# SimpleEXGCircuit.net
KiCad netlist of a schematic drawn in EAGLE
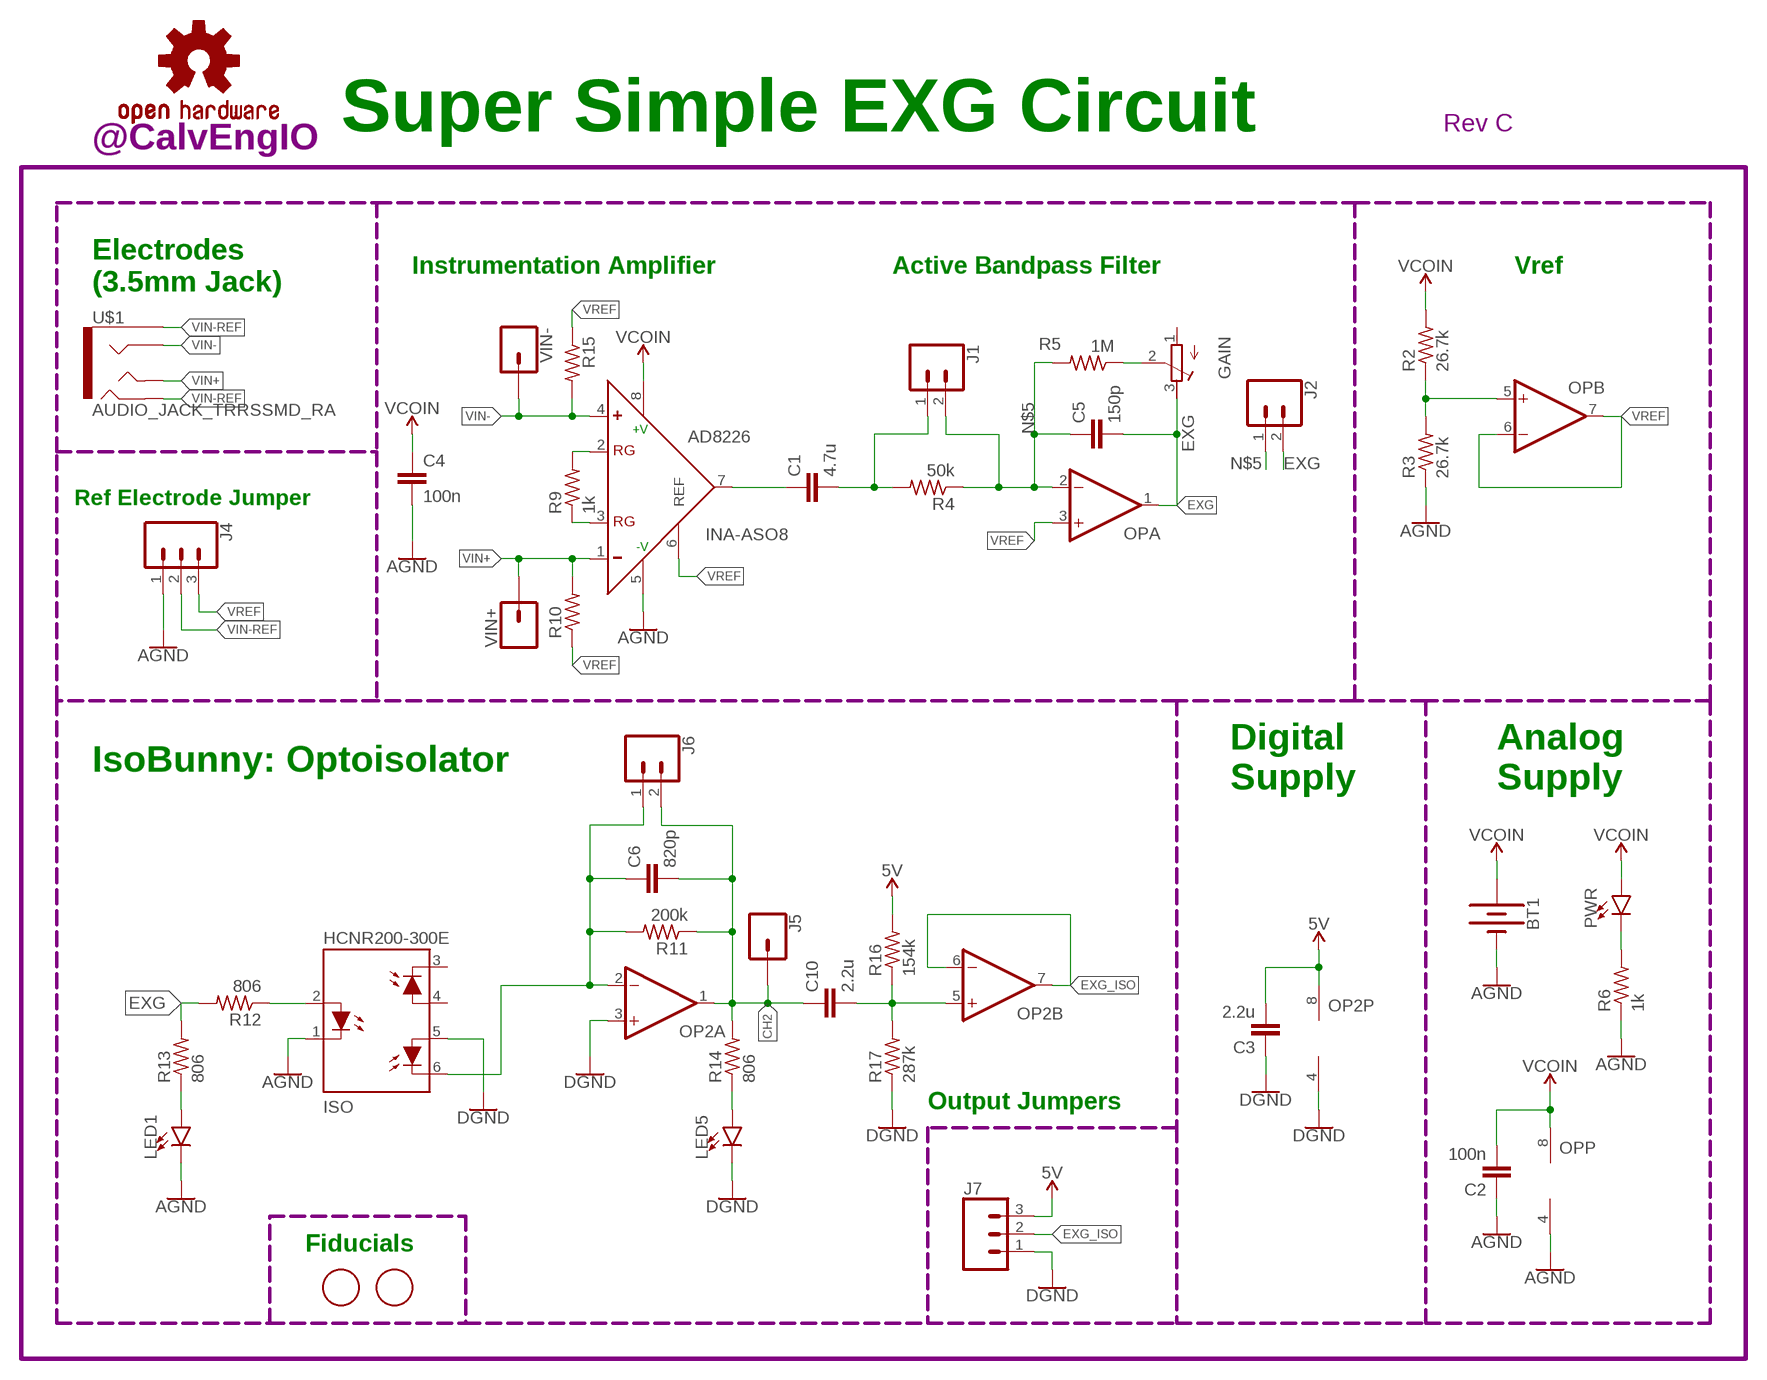
[diagram p0: schematic, sheet 1]

(export (version "E")
  (design (tool "Eeschema 10.0.6"))
  (components
    (comp (ref "AD8226")
      (value "INA-ASO8")
      (footprint "eagle-import:SO8")
      (libsource (lib "eagle-import") (part "INA-ASO8"))
    )
    (comp (ref "BT1")
      (value "BATTERY-20MM_SMD_4LEGS_OVERPASTE")
      (footprint "eagle-import:BATTCON_20MM_4LEGS_OVERPASTE")
      (libsource (lib "eagle-import") (part "BATTERY-20MM_SMD_4LEGS_OVERPASTE"))
    )
    (comp (ref "C1")
      (value "4.7u")
      (footprint "eagle-import:C0603")
      (libsource (lib "eagle-import") (part "CAPACITOR0603"))
    )
    (comp (ref "C2")
      (value "100n")
      (footprint "eagle-import:C0603")
      (libsource (lib "eagle-import") (part "CAPACITOR0603"))
    )
    (comp (ref "C3")
      (value "2.2u")
      (footprint "eagle-import:C0603")
      (libsource (lib "eagle-import") (part "CAPACITOR0603"))
    )
    (comp (ref "C4")
      (value "100n")
      (footprint "eagle-import:C0603")
      (libsource (lib "eagle-import") (part "CAPACITOR0603"))
    )
    (comp (ref "C5")
      (value "150p")
      (footprint "eagle-import:C0603")
      (libsource (lib "eagle-import") (part "CAPACITOR0603"))
    )
    (comp (ref "C6")
      (value "820p")
      (footprint "eagle-import:C0603")
      (libsource (lib "eagle-import") (part "CAPACITOR0603"))
    )
    (comp (ref "C10")
      (value "2.2u")
      (footprint "eagle-import:C0603")
      (libsource (lib "eagle-import") (part "CAPACITOR0603"))
    )
    (comp (ref "GAIN")
      (value "TRIM-POT-P160")
      (footprint "eagle-import:16MMROTARYPOT")
      (libsource (lib "eagle-import") (part "TRIM-POT-P160"))
    )
    (comp (ref "ISO")
      (value "HCNR200-300E")
      (footprint "eagle-import:DIP8-400")
      (libsource (lib "eagle-import") (part "HCNR20-300E0"))
    )
    (comp (ref "J1")
      (value "CONN_02")
      (footprint "eagle-import:1X02")
      (libsource (lib "eagle-import") (part "CONN_02"))
    )
    (comp (ref "J2")
      (value "CONN_02")
      (footprint "eagle-import:1X02")
      (libsource (lib "eagle-import") (part "CONN_02"))
    )
    (comp (ref "J4")
      (value "CONN_03")
      (footprint "eagle-import:1X03")
      (libsource (lib "eagle-import") (part "CONN_03"))
    )
    (comp (ref "J5")
      (value "CONN_01PTH_NO_SILK_KIT")
      (footprint "eagle-import:1X01NS_KIT")
      (libsource (lib "eagle-import") (part "CONN_01PTH_NO_SILK_KIT"))
    )
    (comp (ref "J6")
      (value "CONN_02")
      (footprint "eagle-import:1X02")
      (libsource (lib "eagle-import") (part "CONN_02"))
    )
    (comp (ref "J7")
      (value "CONN_03")
      (footprint "eagle-import:1X03")
      (libsource (lib "eagle-import") (part "CONN_03"))
    )
    (comp (ref "LED1")
      (value "LED1206")
      (footprint "eagle-import:LED-1206")
      (libsource (lib "eagle-import") (part "LED1206"))
    )
    (comp (ref "LED5")
      (value "LED1206")
      (footprint "eagle-import:LED-1206")
      (libsource (lib "eagle-import") (part "LED1206"))
    )
    (comp (ref "LOGO1")
      (value "REVISION.C")
      (footprint "eagle-import:REV.C")
      (libsource (lib "eagle-import") (part "REVISION.C"))
    )
    (comp (ref "LOGO4")
      (value "OSHW-LOGOL")
      (footprint "eagle-import:OSHW-LOGO-L")
      (libsource (lib "eagle-import") (part "OSHW-LOGOL"))
    )
    (comp (ref "OP")
      (value "OP-DUALR")
      (footprint "eagle-import:SO8")
      (fields (field (name "MPN") "AD8607ARMZ-R2"))
      (libsource (lib "eagle-import") (part "OP-DUALR"))
    )
    (comp (ref "OP2")
      (value "OP-DUALR")
      (footprint "eagle-import:SO8")
      (fields (field (name "MPN") "AD8607ARMZ-R2"))
      (libsource (lib "eagle-import") (part "OP-DUALR"))
    )
    (comp (ref "PWR")
      (value "LED1206")
      (footprint "eagle-import:LED-1206")
      (libsource (lib "eagle-import") (part "LED1206"))
    )
    (comp (ref "R2")
      (value "26.7k")
      (footprint "eagle-import:R0603")
      (libsource (lib "eagle-import") (part "RESISTOR0603"))
    )
    (comp (ref "R3")
      (value "26.7k")
      (footprint "eagle-import:R0603")
      (libsource (lib "eagle-import") (part "RESISTOR0603"))
    )
    (comp (ref "R4")
      (value "50k")
      (footprint "eagle-import:R0603")
      (libsource (lib "eagle-import") (part "RESISTOR0603"))
    )
    (comp (ref "R5")
      (value "1M")
      (footprint "eagle-import:R0603")
      (libsource (lib "eagle-import") (part "RESISTOR0603"))
    )
    (comp (ref "R6")
      (value "1k")
      (footprint "eagle-import:R0603")
      (libsource (lib "eagle-import") (part "RESISTOR0603"))
    )
    (comp (ref "R9")
      (value "1k")
      (footprint "eagle-import:R0603")
      (libsource (lib "eagle-import") (part "RESISTOR0603"))
    )
    (comp (ref "R10")
      (value "RESISTOR0603")
      (footprint "eagle-import:R0603")
      (libsource (lib "eagle-import") (part "RESISTOR0603"))
    )
    (comp (ref "R11")
      (value "200k")
      (footprint "eagle-import:R0603")
      (libsource (lib "eagle-import") (part "RESISTOR0603"))
    )
    (comp (ref "R12")
      (value "806")
      (footprint "eagle-import:R0603")
      (libsource (lib "eagle-import") (part "RESISTOR0603"))
    )
    (comp (ref "R13")
      (value "806")
      (footprint "eagle-import:R0603")
      (libsource (lib "eagle-import") (part "RESISTOR0603"))
    )
    (comp (ref "R14")
      (value "806")
      (footprint "eagle-import:R0603")
      (libsource (lib "eagle-import") (part "RESISTOR0603"))
    )
    (comp (ref "R15")
      (value "RESISTOR0603")
      (footprint "eagle-import:R0603")
      (libsource (lib "eagle-import") (part "RESISTOR0603"))
    )
    (comp (ref "R16")
      (value "154k")
      (footprint "eagle-import:R0603")
      (libsource (lib "eagle-import") (part "RESISTOR0603"))
    )
    (comp (ref "R17")
      (value "287k")
      (footprint "eagle-import:R0603")
      (libsource (lib "eagle-import") (part "RESISTOR0603"))
    )
    (comp (ref "U$1")
      (value "AUDIO_JACK_TRRSSMD_RA")
      (footprint "eagle-import:AUDIO_JACK_3.5MM_TRRS_SMD_RA")
      (libsource (lib "eagle-import") (part "AUDIO_JACK_TRRSSMD_RA"))
    )
    (comp (ref "U$4")
      (value "CALVENGIO_HANDLEHANDLE.05")
      (footprint "eagle-import:CALVENGIO_HANDLE.05")
      (libsource (lib "eagle-import") (part "CALVENGIO_HANDLEHANDLE.05"))
    )
    (comp (ref "U$5")
      (value "FIDUCIAL")
      (footprint "eagle-import:FIDUCIAL_1MM")
      (libsource (lib "eagle-import") (part "FIDUCIAL"))
    )
    (comp (ref "U$6")
      (value "FIDUCIAL")
      (footprint "eagle-import:FIDUCIAL_1MM")
      (libsource (lib "eagle-import") (part "FIDUCIAL"))
    )
    (comp (ref "VIN+")
      (value "CONN_01")
      (footprint "eagle-import:1X01")
      (libsource (lib "eagle-import") (part "CONN_01"))
    )
    (comp (ref "VIN-")
      (value "CONN_01")
      (footprint "eagle-import:1X01")
      (libsource (lib "eagle-import") (part "CONN_01"))
    )
  )
  (nets
    (net (code "1") (name "/N$5") (class "Default")
      (node (ref "C5") (pin "1") (pinfunction "1_1") (pintype "passive"))
      (node (ref "J1") (pin "2") (pinfunction "2_2") (pintype "passive"))
      (node (ref "J2") (pin "1") (pinfunction "1_1") (pintype "passive"))
      (node (ref "OP") (pin "2") (pinfunction "-IN_2") (pintype "input"))
      (node (ref "R4") (pin "1") (pinfunction "1_1") (pintype "passive"))
      (node (ref "R5") (pin "2") (pinfunction "2_2") (pintype "passive"))
    )
    (net (code "2") (name "5V") (class "Default")
      (node (ref "C3") (pin "2") (pinfunction "2_2") (pintype "passive"))
      (node (ref "J7") (pin "3") (pinfunction "3_3") (pintype "passive"))
      (node (ref "OP2") (pin "8") (pinfunction "V+_8") (pintype "power_in"))
      (node (ref "R16") (pin "2") (pinfunction "2_2") (pintype "passive"))
    )
    (net (code "3") (name "AGND") (class "Default")
      (node (ref "AD8226") (pin "5") (pinfunction "-V_5") (pintype "power_in"))
      (node (ref "BT1") (pin "2") (pinfunction "-_2") (pintype "power_in"))
      (node (ref "C2") (pin "1") (pinfunction "1_1") (pintype "passive"))
      (node (ref "C4") (pin "2") (pinfunction "2_2") (pintype "passive"))
      (node (ref "ISO") (pin "1") (pinfunction "C_1") (pintype "passive"))
      (node (ref "J4") (pin "1") (pinfunction "1_1") (pintype "passive"))
      (node (ref "LED1") (pin "C") (pinfunction "C_C") (pintype "passive"))
      (node (ref "OP") (pin "4") (pinfunction "V-_4") (pintype "power_in"))
      (node (ref "R3") (pin "1") (pinfunction "1_1") (pintype "passive"))
      (node (ref "R6") (pin "1") (pinfunction "1_1") (pintype "passive"))
    )
    (net (code "4") (name "CH2") (class "Default")
      (node (ref "C10") (pin "1") (pinfunction "1_1") (pintype "passive"))
      (node (ref "C6") (pin "2") (pinfunction "2_2") (pintype "passive"))
      (node (ref "J5") (pin "1") (pinfunction "1_1") (pintype "passive"))
      (node (ref "J6") (pin "2") (pinfunction "2_2") (pintype "passive"))
      (node (ref "OP2") (pin "1") (pinfunction "OUT_1") (pintype "output"))
      (node (ref "R11") (pin "1") (pinfunction "1_1") (pintype "passive"))
      (node (ref "R14") (pin "2") (pinfunction "2_2") (pintype "passive"))
    )
    (net (code "5") (name "DGND") (class "Default")
      (node (ref "C3") (pin "1") (pinfunction "1_1") (pintype "passive"))
      (node (ref "ISO") (pin "5") (pinfunction "A2_5") (pintype "passive"))
      (node (ref "J7") (pin "1") (pinfunction "1_1") (pintype "passive"))
      (node (ref "LED5") (pin "C") (pinfunction "C_C") (pintype "passive"))
      (node (ref "OP2") (pin "3") (pinfunction "+IN_3") (pintype "input"))
      (node (ref "OP2") (pin "4") (pinfunction "V-_4") (pintype "power_in"))
      (node (ref "R17") (pin "1") (pinfunction "1_1") (pintype "passive"))
    )
    (net (code "6") (name "EXG") (class "Default")
      (node (ref "C5") (pin "2") (pinfunction "2_2") (pintype "passive"))
      (node (ref "GAIN") (pin "3") (pinfunction "E_3") (pintype "passive"))
      (node (ref "J2") (pin "2") (pinfunction "2_2") (pintype "passive"))
      (node (ref "OP") (pin "1") (pinfunction "OUT_1") (pintype "output"))
      (node (ref "R12") (pin "2") (pinfunction "2_2") (pintype "passive"))
      (node (ref "R13") (pin "2") (pinfunction "2_2") (pintype "passive"))
    )
    (net (code "7") (name "EXG_ISO") (class "Default")
      (node (ref "J7") (pin "2") (pinfunction "2_2") (pintype "passive"))
      (node (ref "OP2") (pin "6") (pinfunction "-IN_6") (pintype "input"))
      (node (ref "OP2") (pin "7") (pinfunction "OUT_7") (pintype "output"))
    )
    (net (code "8") (name "Net-(AD8226-OUT)") (class "Default")
      (node (ref "AD8226") (pin "7") (pinfunction "OUT_7") (pintype "output"))
      (node (ref "C1") (pin "1") (pinfunction "1_1") (pintype "passive"))
    )
    (net (code "9") (name "Net-(AD8226-RG-Pad2)") (class "Default")
      (node (ref "AD8226") (pin "2") (pinfunction "RG_2") (pintype "passive"))
      (node (ref "R9") (pin "2") (pinfunction "2_2") (pintype "passive"))
    )
    (net (code "10") (name "Net-(AD8226-RG-Pad3)") (class "Default")
      (node (ref "AD8226") (pin "3") (pinfunction "RG_3") (pintype "passive"))
      (node (ref "R9") (pin "1") (pinfunction "1_1") (pintype "passive"))
    )
    (net (code "11") (name "Net-(C1-Pad2)") (class "Default")
      (node (ref "C1") (pin "2") (pinfunction "2_2") (pintype "passive"))
      (node (ref "J1") (pin "1") (pinfunction "1_1") (pintype "passive"))
      (node (ref "R4") (pin "2") (pinfunction "2_2") (pintype "passive"))
    )
    (net (code "12") (name "Net-(GAIN-S)") (class "Default")
      (node (ref "GAIN") (pin "2") (pinfunction "S_2") (pintype "passive"))
      (node (ref "R5") (pin "1") (pinfunction "1_1") (pintype "passive"))
    )
    (net (code "13") (name "Net-(ISO-A)") (class "Default")
      (node (ref "ISO") (pin "2") (pinfunction "A_2") (pintype "passive"))
      (node (ref "R12") (pin "1") (pinfunction "1_1") (pintype "passive"))
    )
    (net (code "14") (name "Net-(ISO-C2)") (class "Default")
      (node (ref "C6") (pin "1") (pinfunction "1_1") (pintype "passive"))
      (node (ref "ISO") (pin "6") (pinfunction "C2_6") (pintype "passive"))
      (node (ref "J6") (pin "1") (pinfunction "1_1") (pintype "passive"))
      (node (ref "OP2") (pin "2") (pinfunction "-IN_2") (pintype "input"))
      (node (ref "R11") (pin "2") (pinfunction "2_2") (pintype "passive"))
    )
    (net (code "15") (name "Net-(LED1-PadA)") (class "Default")
      (node (ref "LED1") (pin "A") (pinfunction "A_A") (pintype "passive"))
      (node (ref "R13") (pin "1") (pinfunction "1_1") (pintype "passive"))
    )
    (net (code "16") (name "Net-(LED5-PadA)") (class "Default")
      (node (ref "LED5") (pin "A") (pinfunction "A_A") (pintype "passive"))
      (node (ref "R14") (pin "1") (pinfunction "1_1") (pintype "passive"))
    )
    (net (code "17") (name "Net-(OP2B-+IN)") (class "Default")
      (node (ref "C10") (pin "2") (pinfunction "2_2") (pintype "passive"))
      (node (ref "OP2") (pin "5") (pinfunction "+IN_5") (pintype "input"))
      (node (ref "R16") (pin "1") (pinfunction "1_1") (pintype "passive"))
      (node (ref "R17") (pin "2") (pinfunction "2_2") (pintype "passive"))
    )
    (net (code "18") (name "Net-(OPB-+IN)") (class "Default")
      (node (ref "OP") (pin "5") (pinfunction "+IN_5") (pintype "input"))
      (node (ref "R2") (pin "1") (pinfunction "1_1") (pintype "passive"))
      (node (ref "R3") (pin "2") (pinfunction "2_2") (pintype "passive"))
    )
    (net (code "19") (name "Net-(PWR-PadC)") (class "Default")
      (node (ref "PWR") (pin "C") (pinfunction "C_C") (pintype "passive"))
      (node (ref "R6") (pin "2") (pinfunction "2_2") (pintype "passive"))
    )
    (net (code "20") (name "VCOIN") (class "Default")
      (node (ref "AD8226") (pin "8") (pinfunction "+V_8") (pintype "power_in"))
      (node (ref "BT1") (pin "1") (pinfunction "+_1") (pintype "power_in"))
      (node (ref "C2") (pin "2") (pinfunction "2_2") (pintype "passive"))
      (node (ref "C4") (pin "1") (pinfunction "1_1") (pintype "passive"))
      (node (ref "OP") (pin "8") (pinfunction "V+_8") (pintype "power_in"))
      (node (ref "PWR") (pin "A") (pinfunction "A_A") (pintype "passive"))
      (node (ref "R2") (pin "2") (pinfunction "2_2") (pintype "passive"))
    )
    (net (code "21") (name "VIN+") (class "Default")
      (node (ref "AD8226") (pin "1") (pinfunction "IN-_1") (pintype "input"))
      (node (ref "R10") (pin "2") (pinfunction "2_2") (pintype "passive"))
      (node (ref "U$1") (pin "TIP") (pinfunction "TIP_TIP") (pintype "bidirectional"))
      (node (ref "VIN+") (pin "1") (pinfunction "1_1") (pintype "passive"))
    )
    (net (code "22") (name "VIN-") (class "Default")
      (node (ref "AD8226") (pin "4") (pinfunction "IN+_4") (pintype "input"))
      (node (ref "R15") (pin "2") (pinfunction "2_2") (pintype "passive"))
      (node (ref "U$1") (pin "RING1") (pinfunction "RING1_RING1") (pintype "bidirectional"))
      (node (ref "VIN-") (pin "1") (pinfunction "1_1") (pintype "passive"))
    )
    (net (code "23") (name "VIN-REF") (class "Default")
      (node (ref "J4") (pin "2") (pinfunction "2_2") (pintype "passive"))
      (node (ref "U$1") (pin "EARTH") (pinfunction "EARTH_EARTH") (pintype "bidirectional"))
      (node (ref "U$1") (pin "RING2") (pinfunction "RING2_RING2") (pintype "bidirectional"))
    )
    (net (code "24") (name "VREF") (class "Default")
      (node (ref "AD8226") (pin "6") (pinfunction "REF_6") (pintype "passive"))
      (node (ref "J4") (pin "3") (pinfunction "3_3") (pintype "passive"))
      (node (ref "OP") (pin "3") (pinfunction "+IN_3") (pintype "input"))
      (node (ref "OP") (pin "6") (pinfunction "-IN_6") (pintype "input"))
      (node (ref "OP") (pin "7") (pinfunction "OUT_7") (pintype "output"))
      (node (ref "R10") (pin "1") (pinfunction "1_1") (pintype "passive"))
      (node (ref "R15") (pin "1") (pinfunction "1_1") (pintype "passive"))
    )
    (net (code "25") (name "unconnected-(GAIN-A-Pad1)") (class "Default")
      (node (ref "GAIN") (pin "1") (pinfunction "A_1") (pintype "passive"))
    )
    (net (code "26") (name "unconnected-(ISO-A1-Pad4)") (class "Default")
      (node (ref "ISO") (pin "4") (pinfunction "A1_4") (pintype "passive"))
    )
    (net (code "27") (name "unconnected-(ISO-C1-Pad3)") (class "Default")
      (node (ref "ISO") (pin "3") (pinfunction "C1_3") (pintype "passive"))
    )
  )
)
